# STM8S207R8T6_Header_Board.net
KiCad netlist of a schematic drawn in Altium Designer
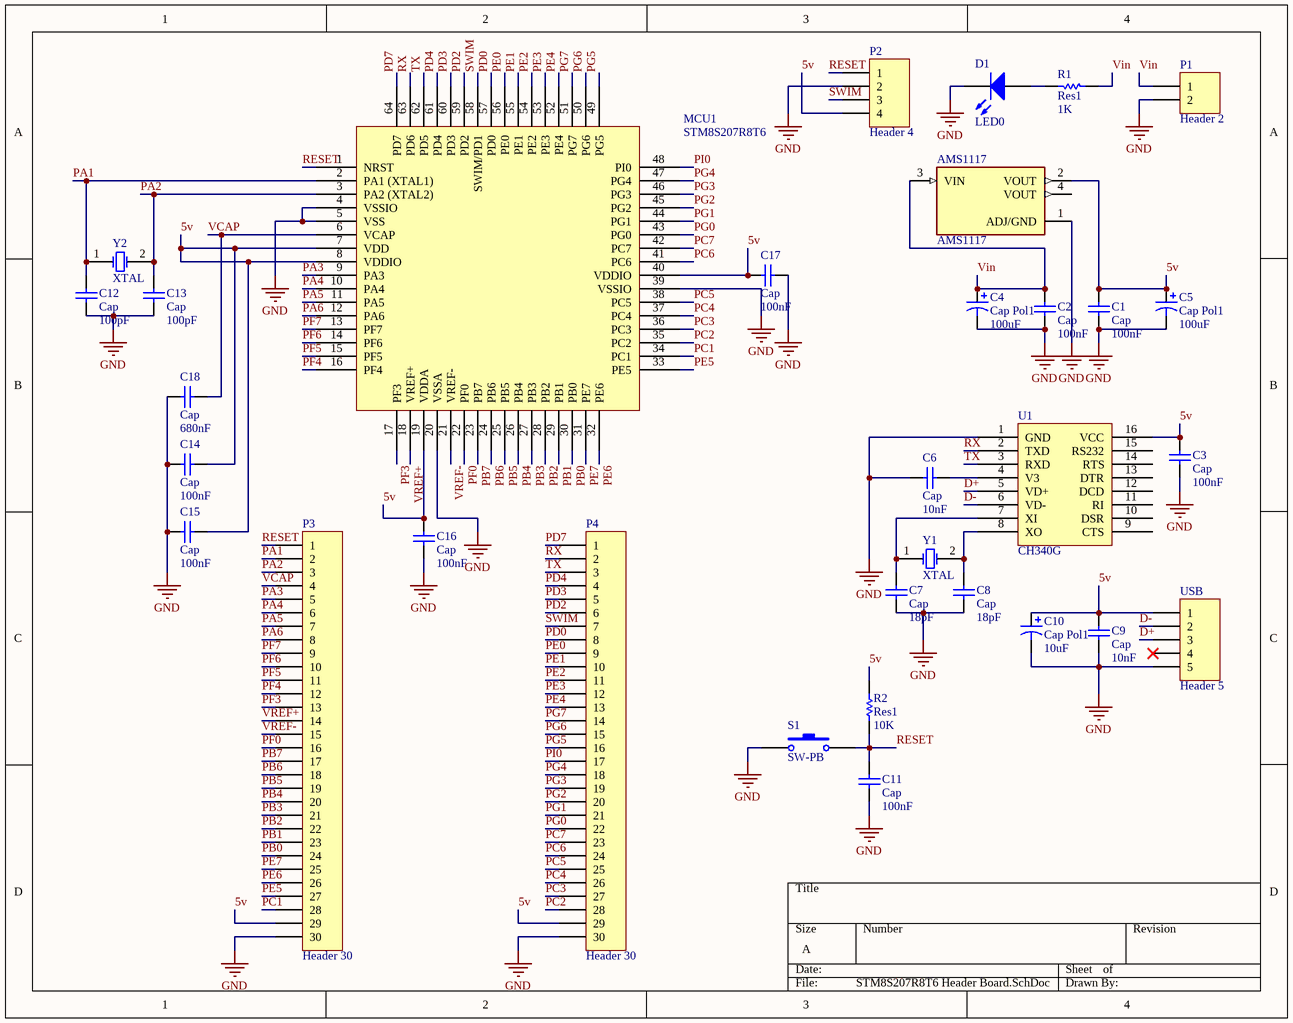
[diagram p0: STM8S207R8T6 Header Board.SchDoc]

(export (version "E")
  (design (tool "Eeschema 10.0.6"))
  (components
    (comp (ref "AMS1117")
      (value "AMS1117")
      (footprint "SOT229P700X180-4N")
      (description "UNO PLUS Arduino R3 Shield, Xbee Arduino IDE Wheeled Robotics Kit")
      (fields (field (name "MF") "Seeed Technology"))
      (libsource (lib "AMS1117") (part "AMS1117"))
    )
    (comp (ref "C1")
      (value "Cap")
      (footprint "6-0805_N")
      (description "Capacitor")
      (fields (field (name "ALTIUM_VALUE") "100nF") (field (name "PUBLISHER") "Altium Limited"))
      (libsource (lib "Miscellaneous Devices") (part "Cap"))
    )
    (comp (ref "C2")
      (value "Cap")
      (footprint "6-0805_N")
      (description "Capacitor")
      (fields (field (name "ALTIUM_VALUE") "100nF") (field (name "PUBLISHER") "Altium Limited"))
      (libsource (lib "Miscellaneous Devices") (part "Cap"))
    )
    (comp (ref "C3")
      (value "Cap")
      (footprint "6-0805_N")
      (description "Capacitor")
      (fields (field (name "ALTIUM_VALUE") "100nF") (field (name "PUBLISHER") "Altium Limited"))
      (libsource (lib "Miscellaneous Devices") (part "Cap"))
    )
    (comp (ref "C4")
      (value "Cap Pol1")
      (footprint "C1210_N")
      (description "Polarized Capacitor (Radial)")
      (fields (field (name "ALTIUM_VALUE") "100uF") (field (name "PUBLISHER") "Altium Limited"))
      (libsource (lib "Miscellaneous Devices") (part "Cap Pol1"))
    )
    (comp (ref "C5")
      (value "Cap Pol1")
      (footprint "C1210_N")
      (description "Polarized Capacitor (Radial)")
      (fields (field (name "ALTIUM_VALUE") "100uF") (field (name "PUBLISHER") "Altium Limited"))
      (libsource (lib "Miscellaneous Devices") (part "Cap Pol1"))
    )
    (comp (ref "C6")
      (value "Cap")
      (footprint "6-0805_N")
      (description "Capacitor")
      (fields (field (name "ALTIUM_VALUE") "10nF") (field (name "PUBLISHER") "Altium Limited"))
      (libsource (lib "Miscellaneous Devices") (part "Cap"))
    )
    (comp (ref "C7")
      (value "Cap")
      (footprint "6-0805_N")
      (description "Capacitor")
      (fields (field (name "ALTIUM_VALUE") "18pF") (field (name "PUBLISHER") "Altium Limited"))
      (libsource (lib "Miscellaneous Devices") (part "Cap"))
    )
    (comp (ref "C8")
      (value "Cap")
      (footprint "6-0805_N")
      (description "Capacitor")
      (fields (field (name "ALTIUM_VALUE") "18pF") (field (name "PUBLISHER") "Altium Limited"))
      (libsource (lib "Miscellaneous Devices") (part "Cap"))
    )
    (comp (ref "C9")
      (value "Cap")
      (footprint "6-0805_N")
      (description "Capacitor")
      (fields (field (name "ALTIUM_VALUE") "10nF") (field (name "PUBLISHER") "Altium Limited"))
      (libsource (lib "Miscellaneous Devices") (part "Cap"))
    )
    (comp (ref "C10")
      (value "Cap Pol1")
      (footprint "C1210_N")
      (description "Polarized Capacitor (Radial)")
      (fields (field (name "ALTIUM_VALUE") "10uF") (field (name "PUBLISHER") "Altium Limited"))
      (libsource (lib "Miscellaneous Devices") (part "Cap Pol1"))
    )
    (comp (ref "C11")
      (value "Cap")
      (footprint "6-0805_N")
      (description "Capacitor")
      (fields (field (name "ALTIUM_VALUE") "100nF") (field (name "PUBLISHER") "Altium Limited"))
      (libsource (lib "Miscellaneous Devices") (part "Cap"))
    )
    (comp (ref "C12")
      (value "Cap")
      (footprint "6-0805_N")
      (description "Capacitor")
      (fields (field (name "ALTIUM_VALUE") "100pF") (field (name "PUBLISHER") "Altium Limited"))
      (libsource (lib "Miscellaneous Devices") (part "Cap"))
    )
    (comp (ref "C13")
      (value "Cap")
      (footprint "6-0805_N")
      (description "Capacitor")
      (fields (field (name "ALTIUM_VALUE") "100pF") (field (name "PUBLISHER") "Altium Limited"))
      (libsource (lib "Miscellaneous Devices") (part "Cap"))
    )
    (comp (ref "C14")
      (value "Cap")
      (footprint "6-0805_N")
      (description "Capacitor")
      (fields (field (name "ALTIUM_VALUE") "100nF") (field (name "PUBLISHER") "Altium Limited"))
      (libsource (lib "Miscellaneous Devices") (part "Cap"))
    )
    (comp (ref "C15")
      (value "Cap")
      (footprint "6-0805_N")
      (description "Capacitor")
      (fields (field (name "ALTIUM_VALUE") "100nF") (field (name "PUBLISHER") "Altium Limited"))
      (libsource (lib "Miscellaneous Devices") (part "Cap"))
    )
    (comp (ref "C16")
      (value "Cap")
      (footprint "6-0805_N")
      (description "Capacitor")
      (fields (field (name "ALTIUM_VALUE") "100nF") (field (name "PUBLISHER") "Altium Limited"))
      (libsource (lib "Miscellaneous Devices") (part "Cap"))
    )
    (comp (ref "C17")
      (value "Cap")
      (footprint "6-0805_N")
      (description "Capacitor")
      (fields (field (name "ALTIUM_VALUE") "100nF") (field (name "PUBLISHER") "Altium Limited"))
      (libsource (lib "Miscellaneous Devices") (part "Cap"))
    )
    (comp (ref "C18")
      (value "Cap")
      (footprint "6-0805_N")
      (description "Capacitor")
      (fields (field (name "ALTIUM_VALUE") "680nF") (field (name "PUBLISHER") "Altium Limited"))
      (libsource (lib "Miscellaneous Devices") (part "Cap"))
    )
    (comp (ref "D1")
      (value "LED0")
      (footprint "6-0805_N")
      (description "Typical INFRARED GaAs LED")
      (fields (field (name "PUBLISHER") "Altium Limited"))
      (libsource (lib "Miscellaneous Devices") (part "LED0"))
    )
    (comp (ref "MCU1")
      (value "STM8S207R8T6")
      (footprint "QFP50P1200X1200X160-64N")
      (libsource (lib "STM8S207R8T6") (part "STM8S207R8T6"))
    )
    (comp (ref "P1")
      (value "Header 2")
      (footprint "Terminal2")
      (description "Header, 2-Pin")
      (fields (field (name "PUBLISHER") "Altium Limited"))
      (libsource (lib "Miscellaneous Connectors") (part "Header 2"))
    )
    (comp (ref "P2")
      (value "Header 4")
      (footprint "HDR1X4")
      (description "Header, 4-Pin")
      (fields (field (name "PUBLISHER") "Altium Limited"))
      (libsource (lib "Miscellaneous Connectors") (part "Header 4"))
    )
    (comp (ref "P3")
      (value "Header 30")
      (footprint "Header 30")
      (description "Header, 30-Pin")
      (fields (field (name "PUBLISHER") "Altium Limited"))
      (libsource (lib "Miscellaneous Connectors") (part "Header 30"))
    )
    (comp (ref "P4")
      (value "Header 30")
      (footprint "Header 30")
      (description "Header, 30-Pin")
      (fields (field (name "PUBLISHER") "Altium Limited"))
      (libsource (lib "Miscellaneous Connectors") (part "Header 30"))
    )
    (comp (ref "R1")
      (value "Res1")
      (footprint "6-0805_N")
      (description "Resistor")
      (fields (field (name "ALTIUM_VALUE") "1K") (field (name "PUBLISHER") "Altium Limited"))
      (libsource (lib "Miscellaneous Devices") (part "Res1"))
    )
    (comp (ref "R2")
      (value "Res1")
      (footprint "6-0805_N")
      (description "Resistor")
      (fields (field (name "ALTIUM_VALUE") "10K") (field (name "PUBLISHER") "Altium Limited"))
      (libsource (lib "Miscellaneous Devices") (part "Res1"))
    )
    (comp (ref "S1")
      (value "SW-PB")
      (footprint "RES_B")
      (description "Switch")
      (fields (field (name "PUBLISHER") "Altium Limited"))
      (libsource (lib "Miscellaneous Devices") (part "SW-PB"))
    )
    (comp (ref "U1")
      (value "CH340G")
      (footprint "SOIC127P600X175-16N")
      (libsource (lib "CH340") (part "CH340G"))
    )
    (comp (ref "USB")
      (value "Header 5")
      (footprint "TE_3-1734035-2")
      (description "Header, 5-Pin")
      (fields (field (name "PUBLISHER") "Altium Limited"))
      (libsource (lib "Miscellaneous Connectors") (part "Header 5"))
    )
    (comp (ref "Y1")
      (value "XTAL")
      (footprint "Xtal")
      (description "Crystal Oscillator")
      (fields (field (name "PUBLISHER") "Altium Limited"))
      (libsource (lib "Miscellaneous Devices") (part "XTAL"))
    )
    (comp (ref "Y2")
      (value "XTAL")
      (footprint "Xtal")
      (description "Crystal Oscillator")
      (fields (field (name "PUBLISHER") "Altium Limited"))
      (libsource (lib "Miscellaneous Devices") (part "XTAL"))
    )
  )
  (nets
    (net (code "1") (name "/5v") (class "Default")
      (node (ref "AMS1117") (pin "2") (pinfunction "VOUT_2") (pintype "output"))
      (node (ref "C1") (pin "2") (pinfunction "2_2") (pintype "passive"))
      (node (ref "C10") (pin "1") (pinfunction "1_1") (pintype "passive"))
      (node (ref "C14") (pin "1") (pinfunction "1_1") (pintype "passive"))
      (node (ref "C15") (pin "1") (pinfunction "1_1") (pintype "passive"))
      (node (ref "C16") (pin "2") (pinfunction "2_2") (pintype "passive"))
      (node (ref "C17") (pin "1") (pinfunction "1_1") (pintype "passive"))
      (node (ref "C3") (pin "1") (pinfunction "1_1") (pintype "passive"))
      (node (ref "C5") (pin "1") (pinfunction "1_1") (pintype "passive"))
      (node (ref "C9") (pin "2") (pinfunction "2_2") (pintype "passive"))
      (node (ref "MCU1") (pin "19") (pinfunction "VDDA_19") (pintype "passive"))
      (node (ref "MCU1") (pin "40") (pinfunction "VDDIO_40") (pintype "passive"))
      (node (ref "MCU1") (pin "7") (pinfunction "VDD_7") (pintype "passive"))
      (node (ref "MCU1") (pin "8") (pinfunction "VDDIO_8") (pintype "passive"))
      (node (ref "P2") (pin "4") (pinfunction "4_4") (pintype "passive"))
      (node (ref "P3") (pin "29") (pinfunction "29_29") (pintype "passive"))
      (node (ref "P4") (pin "29") (pinfunction "29_29") (pintype "passive"))
      (node (ref "R2") (pin "2") (pinfunction "2_2") (pintype "passive"))
      (node (ref "U1") (pin "16") (pinfunction "VCC_16") (pintype "passive"))
      (node (ref "USB") (pin "1") (pinfunction "1_1") (pintype "passive"))
    )
    (net (code "2") (name "/D+") (class "Default")
      (node (ref "U1") (pin "5") (pinfunction "VD+_5") (pintype "passive"))
      (node (ref "USB") (pin "3") (pinfunction "3_3") (pintype "passive"))
    )
    (net (code "3") (name "/D-") (class "Default")
      (node (ref "U1") (pin "6") (pinfunction "VD-_6") (pintype "passive"))
      (node (ref "USB") (pin "2") (pinfunction "2_2") (pintype "passive"))
    )
    (net (code "4") (name "/PA1") (class "Default")
      (node (ref "C12") (pin "2") (pinfunction "2_2") (pintype "passive"))
      (node (ref "MCU1") (pin "2") (pinfunction "PA1_(XTAL1)_2") (pintype "passive"))
      (node (ref "P3") (pin "2") (pinfunction "2_2") (pintype "passive"))
      (node (ref "Y2") (pin "1") (pinfunction "OSC1_1") (pintype "passive"))
    )
    (net (code "5") (name "/PA2") (class "Default")
      (node (ref "C13") (pin "2") (pinfunction "2_2") (pintype "passive"))
      (node (ref "MCU1") (pin "3") (pinfunction "PA2_(XTAL2)_3") (pintype "passive"))
      (node (ref "P3") (pin "3") (pinfunction "3_3") (pintype "passive"))
      (node (ref "Y2") (pin "2") (pinfunction "OSC2_2") (pintype "passive"))
    )
    (net (code "6") (name "/PA3") (class "Default")
      (node (ref "MCU1") (pin "9") (pinfunction "PA3_9") (pintype "passive"))
      (node (ref "P3") (pin "5") (pinfunction "5_5") (pintype "passive"))
    )
    (net (code "7") (name "/PA4") (class "Default")
      (node (ref "MCU1") (pin "10") (pinfunction "PA4_10") (pintype "passive"))
      (node (ref "P3") (pin "6") (pinfunction "6_6") (pintype "passive"))
    )
    (net (code "8") (name "/PA5") (class "Default")
      (node (ref "MCU1") (pin "11") (pinfunction "PA5_11") (pintype "passive"))
      (node (ref "P3") (pin "7") (pinfunction "7_7") (pintype "passive"))
    )
    (net (code "9") (name "/PA6") (class "Default")
      (node (ref "MCU1") (pin "12") (pinfunction "PA6_12") (pintype "passive"))
      (node (ref "P3") (pin "8") (pinfunction "8_8") (pintype "passive"))
    )
    (net (code "10") (name "/PB0") (class "Default")
      (node (ref "MCU1") (pin "30") (pinfunction "PB0_30") (pintype "passive"))
      (node (ref "P3") (pin "24") (pinfunction "24_24") (pintype "passive"))
    )
    (net (code "11") (name "/PB1") (class "Default")
      (node (ref "MCU1") (pin "29") (pinfunction "PB1_29") (pintype "passive"))
      (node (ref "P3") (pin "23") (pinfunction "23_23") (pintype "passive"))
    )
    (net (code "12") (name "/PB2") (class "Default")
      (node (ref "MCU1") (pin "28") (pinfunction "PB2_28") (pintype "passive"))
      (node (ref "P3") (pin "22") (pinfunction "22_22") (pintype "passive"))
    )
    (net (code "13") (name "/PB3") (class "Default")
      (node (ref "MCU1") (pin "27") (pinfunction "PB3_27") (pintype "passive"))
      (node (ref "P3") (pin "21") (pinfunction "21_21") (pintype "passive"))
    )
    (net (code "14") (name "/PB4") (class "Default")
      (node (ref "MCU1") (pin "26") (pinfunction "PB4_26") (pintype "passive"))
      (node (ref "P3") (pin "20") (pinfunction "20_20") (pintype "passive"))
    )
    (net (code "15") (name "/PB5") (class "Default")
      (node (ref "MCU1") (pin "25") (pinfunction "PB5_25") (pintype "passive"))
      (node (ref "P3") (pin "19") (pinfunction "19_19") (pintype "passive"))
    )
    (net (code "16") (name "/PB6") (class "Default")
      (node (ref "MCU1") (pin "24") (pinfunction "PB6_24") (pintype "passive"))
      (node (ref "P3") (pin "18") (pinfunction "18_18") (pintype "passive"))
    )
    (net (code "17") (name "/PB7") (class "Default")
      (node (ref "MCU1") (pin "23") (pinfunction "PB7_23") (pintype "passive"))
      (node (ref "P3") (pin "17") (pinfunction "17_17") (pintype "passive"))
    )
    (net (code "18") (name "/PC1") (class "Default")
      (node (ref "MCU1") (pin "34") (pinfunction "PC1_34") (pintype "passive"))
      (node (ref "P3") (pin "28") (pinfunction "28_28") (pintype "passive"))
    )
    (net (code "19") (name "/PC2") (class "Default")
      (node (ref "MCU1") (pin "35") (pinfunction "PC2_35") (pintype "passive"))
      (node (ref "P4") (pin "28") (pinfunction "28_28") (pintype "passive"))
    )
    (net (code "20") (name "/PC3") (class "Default")
      (node (ref "MCU1") (pin "36") (pinfunction "PC3_36") (pintype "passive"))
      (node (ref "P4") (pin "27") (pinfunction "27_27") (pintype "passive"))
    )
    (net (code "21") (name "/PC4") (class "Default")
      (node (ref "MCU1") (pin "37") (pinfunction "PC4_37") (pintype "passive"))
      (node (ref "P4") (pin "26") (pinfunction "26_26") (pintype "passive"))
    )
    (net (code "22") (name "/PC5") (class "Default")
      (node (ref "MCU1") (pin "38") (pinfunction "PC5_38") (pintype "passive"))
      (node (ref "P4") (pin "25") (pinfunction "25_25") (pintype "passive"))
    )
    (net (code "23") (name "/PC6") (class "Default")
      (node (ref "MCU1") (pin "41") (pinfunction "PC6_41") (pintype "passive"))
      (node (ref "P4") (pin "24") (pinfunction "24_24") (pintype "passive"))
    )
    (net (code "24") (name "/PC7") (class "Default")
      (node (ref "MCU1") (pin "42") (pinfunction "PC7_42") (pintype "passive"))
      (node (ref "P4") (pin "23") (pinfunction "23_23") (pintype "passive"))
    )
    (net (code "25") (name "/PD0") (class "Default")
      (node (ref "MCU1") (pin "57") (pinfunction "PD0_57") (pintype "passive"))
      (node (ref "P4") (pin "8") (pinfunction "8_8") (pintype "passive"))
    )
    (net (code "26") (name "/PD2") (class "Default")
      (node (ref "MCU1") (pin "59") (pinfunction "PD2_59") (pintype "passive"))
      (node (ref "P4") (pin "6") (pinfunction "6_6") (pintype "passive"))
    )
    (net (code "27") (name "/PD3") (class "Default")
      (node (ref "MCU1") (pin "60") (pinfunction "PD3_60") (pintype "passive"))
      (node (ref "P4") (pin "5") (pinfunction "5_5") (pintype "passive"))
    )
    (net (code "28") (name "/PD4") (class "Default")
      (node (ref "MCU1") (pin "61") (pinfunction "PD4_61") (pintype "passive"))
      (node (ref "P4") (pin "4") (pinfunction "4_4") (pintype "passive"))
    )
    (net (code "29") (name "/PD7") (class "Default")
      (node (ref "MCU1") (pin "64") (pinfunction "PD7_64") (pintype "passive"))
      (node (ref "P4") (pin "1") (pinfunction "1_1") (pintype "passive"))
    )
    (net (code "30") (name "/PE0") (class "Default")
      (node (ref "MCU1") (pin "56") (pinfunction "PE0_56") (pintype "passive"))
      (node (ref "P4") (pin "9") (pinfunction "9_9") (pintype "passive"))
    )
    (net (code "31") (name "/PE1") (class "Default")
      (node (ref "MCU1") (pin "55") (pinfunction "PE1_55") (pintype "passive"))
      (node (ref "P4") (pin "10") (pinfunction "10_10") (pintype "passive"))
    )
    (net (code "32") (name "/PE2") (class "Default")
      (node (ref "MCU1") (pin "54") (pinfunction "PE2_54") (pintype "passive"))
      (node (ref "P4") (pin "11") (pinfunction "11_11") (pintype "passive"))
    )
    (net (code "33") (name "/PE3") (class "Default")
      (node (ref "MCU1") (pin "53") (pinfunction "PE3_53") (pintype "passive"))
      (node (ref "P4") (pin "12") (pinfunction "12_12") (pintype "passive"))
    )
    (net (code "34") (name "/PE4") (class "Default")
      (node (ref "MCU1") (pin "52") (pinfunction "PE4_52") (pintype "passive"))
      (node (ref "P4") (pin "13") (pinfunction "13_13") (pintype "passive"))
    )
    (net (code "35") (name "/PE5") (class "Default")
      (node (ref "MCU1") (pin "33") (pinfunction "PE5_33") (pintype "passive"))
      (node (ref "P3") (pin "27") (pinfunction "27_27") (pintype "passive"))
    )
    (net (code "36") (name "/PE6") (class "Default")
      (node (ref "MCU1") (pin "32") (pinfunction "PE6_32") (pintype "passive"))
      (node (ref "P3") (pin "26") (pinfunction "26_26") (pintype "passive"))
    )
    (net (code "37") (name "/PE7") (class "Default")
      (node (ref "MCU1") (pin "31") (pinfunction "PE7_31") (pintype "passive"))
      (node (ref "P3") (pin "25") (pinfunction "25_25") (pintype "passive"))
    )
    (net (code "38") (name "/PF0") (class "Default")
      (node (ref "MCU1") (pin "22") (pinfunction "PF0_22") (pintype "passive"))
      (node (ref "P3") (pin "16") (pinfunction "16_16") (pintype "passive"))
    )
    (net (code "39") (name "/PF3") (class "Default")
      (node (ref "MCU1") (pin "17") (pinfunction "PF3_17") (pintype "passive"))
      (node (ref "P3") (pin "13") (pinfunction "13_13") (pintype "passive"))
    )
    (net (code "40") (name "/PF4") (class "Default")
      (node (ref "MCU1") (pin "16") (pinfunction "PF4_16") (pintype "passive"))
      (node (ref "P3") (pin "12") (pinfunction "12_12") (pintype "passive"))
    )
    (net (code "41") (name "/PF5") (class "Default")
      (node (ref "MCU1") (pin "15") (pinfunction "PF5_15") (pintype "passive"))
      (node (ref "P3") (pin "11") (pinfunction "11_11") (pintype "passive"))
    )
    (net (code "42") (name "/PF6") (class "Default")
      (node (ref "MCU1") (pin "14") (pinfunction "PF6_14") (pintype "passive"))
      (node (ref "P3") (pin "10") (pinfunction "10_10") (pintype "passive"))
    )
    (net (code "43") (name "/PF7") (class "Default")
      (node (ref "MCU1") (pin "13") (pinfunction "PF7_13") (pintype "passive"))
      (node (ref "P3") (pin "9") (pinfunction "9_9") (pintype "passive"))
    )
    (net (code "44") (name "/PG0") (class "Default")
      (node (ref "MCU1") (pin "43") (pinfunction "PG0_43") (pintype "passive"))
      (node (ref "P4") (pin "22") (pinfunction "22_22") (pintype "passive"))
    )
    (net (code "45") (name "/PG1") (class "Default")
      (node (ref "MCU1") (pin "44") (pinfunction "PG1_44") (pintype "passive"))
      (node (ref "P4") (pin "21") (pinfunction "21_21") (pintype "passive"))
    )
    (net (code "46") (name "/PG2") (class "Default")
      (node (ref "MCU1") (pin "45") (pinfunction "PG2_45") (pintype "passive"))
      (node (ref "P4") (pin "20") (pinfunction "20_20") (pintype "passive"))
    )
    (net (code "47") (name "/PG3") (class "Default")
      (node (ref "MCU1") (pin "46") (pinfunction "PG3_46") (pintype "passive"))
      (node (ref "P4") (pin "19") (pinfunction "19_19") (pintype "passive"))
    )
    (net (code "48") (name "/PG4") (class "Default")
      (node (ref "MCU1") (pin "47") (pinfunction "PG4_47") (pintype "passive"))
      (node (ref "P4") (pin "18") (pinfunction "18_18") (pintype "passive"))
    )
    (net (code "49") (name "/PG5") (class "Default")
      (node (ref "MCU1") (pin "49") (pinfunction "PG5_49") (pintype "passive"))
      (node (ref "P4") (pin "16") (pinfunction "16_16") (pintype "passive"))
    )
    (net (code "50") (name "/PG6") (class "Default")
      (node (ref "MCU1") (pin "50") (pinfunction "PG6_50") (pintype "passive"))
      (node (ref "P4") (pin "15") (pinfunction "15_15") (pintype "passive"))
    )
    (net (code "51") (name "/PG7") (class "Default")
      (node (ref "MCU1") (pin "51") (pinfunction "PG7_51") (pintype "passive"))
      (node (ref "P4") (pin "14") (pinfunction "14_14") (pintype "passive"))
    )
    (net (code "52") (name "/PI0") (class "Default")
      (node (ref "MCU1") (pin "48") (pinfunction "PI0_48") (pintype "passive"))
      (node (ref "P4") (pin "17") (pinfunction "17_17") (pintype "passive"))
    )
    (net (code "53") (name "/RESET") (class "Default")
      (node (ref "C11") (pin "2") (pinfunction "2_2") (pintype "passive"))
      (node (ref "MCU1") (pin "1") (pinfunction "NRST_1") (pintype "passive"))
      (node (ref "P2") (pin "1") (pinfunction "1_1") (pintype "passive"))
      (node (ref "P3") (pin "1") (pinfunction "1_1") (pintype "passive"))
      (node (ref "R2") (pin "1") (pinfunction "1_1") (pintype "passive"))
      (node (ref "S1") (pin "2") (pinfunction "2_2") (pintype "passive"))
    )
    (net (code "54") (name "/RX") (class "Default")
      (node (ref "MCU1") (pin "63") (pinfunction "PD6_63") (pintype "passive"))
      (node (ref "P4") (pin "2") (pinfunction "2_2") (pintype "passive"))
      (node (ref "U1") (pin "2") (pinfunction "TXD_2") (pintype "passive"))
    )
    (net (code "55") (name "/SWIM") (class "Default")
      (node (ref "MCU1") (pin "58") (pinfunction "SWIM/PD1_58") (pintype "passive"))
      (node (ref "P2") (pin "3") (pinfunction "3_3") (pintype "passive"))
      (node (ref "P4") (pin "7") (pinfunction "7_7") (pintype "passive"))
    )
    (net (code "56") (name "/TX") (class "Default")
      (node (ref "MCU1") (pin "62") (pinfunction "PD5_62") (pintype "passive"))
      (node (ref "P4") (pin "3") (pinfunction "3_3") (pintype "passive"))
      (node (ref "U1") (pin "3") (pinfunction "RXD_3") (pintype "passive"))
    )
    (net (code "57") (name "/VCAP") (class "Default")
      (node (ref "C18") (pin "1") (pinfunction "1_1") (pintype "passive"))
      (node (ref "MCU1") (pin "6") (pinfunction "VCAP_6") (pintype "passive"))
      (node (ref "P3") (pin "4") (pinfunction "4_4") (pintype "passive"))
    )
    (net (code "58") (name "/VREF+") (class "Default")
      (node (ref "MCU1") (pin "18") (pinfunction "VREF+_18") (pintype "passive"))
      (node (ref "P3") (pin "14") (pinfunction "14_14") (pintype "passive"))
    )
    (net (code "59") (name "/VREF-") (class "Default")
      (node (ref "MCU1") (pin "21") (pinfunction "VREF-_21") (pintype "passive"))
      (node (ref "P3") (pin "15") (pinfunction "15_15") (pintype "passive"))
    )
    (net (code "60") (name "/Vin") (class "Default")
      (node (ref "AMS1117") (pin "3") (pinfunction "VIN_3") (pintype "input"))
      (node (ref "C2") (pin "2") (pinfunction "2_2") (pintype "passive"))
      (node (ref "C4") (pin "1") (pinfunction "1_1") (pintype "passive"))
      (node (ref "P1") (pin "1") (pinfunction "1_1") (pintype "passive"))
      (node (ref "R1") (pin "1") (pinfunction "1_1") (pintype "passive"))
    )
    (net (code "61") (name "GND") (class "Default")
      (node (ref "AMS1117") (pin "1") (pinfunction "ADJ/GND_1") (pintype "power_in"))
      (node (ref "C1") (pin "1") (pinfunction "1_1") (pintype "passive"))
      (node (ref "C10") (pin "2") (pinfunction "2_2") (pintype "passive"))
      (node (ref "C11") (pin "1") (pinfunction "1_1") (pintype "passive"))
      (node (ref "C12") (pin "1") (pinfunction "1_1") (pintype "passive"))
      (node (ref "C13") (pin "1") (pinfunction "1_1") (pintype "passive"))
      (node (ref "C14") (pin "2") (pinfunction "2_2") (pintype "passive"))
      (node (ref "C15") (pin "2") (pinfunction "2_2") (pintype "passive"))
      (node (ref "C16") (pin "1") (pinfunction "1_1") (pintype "passive"))
      (node (ref "C17") (pin "2") (pinfunction "2_2") (pintype "passive"))
      (node (ref "C18") (pin "2") (pinfunction "2_2") (pintype "passive"))
      (node (ref "C2") (pin "1") (pinfunction "1_1") (pintype "passive"))
      (node (ref "C3") (pin "2") (pinfunction "2_2") (pintype "passive"))
      (node (ref "C4") (pin "2") (pinfunction "2_2") (pintype "passive"))
      (node (ref "C5") (pin "2") (pinfunction "2_2") (pintype "passive"))
      (node (ref "C6") (pin "1") (pinfunction "1_1") (pintype "passive"))
      (node (ref "C7") (pin "1") (pinfunction "1_1") (pintype "passive"))
      (node (ref "C8") (pin "1") (pinfunction "1_1") (pintype "passive"))
      (node (ref "C9") (pin "1") (pinfunction "1_1") (pintype "passive"))
      (node (ref "D1") (pin "2") (pinfunction "K_2") (pintype "passive"))
      (node (ref "MCU1") (pin "20") (pinfunction "VSSA_20") (pintype "passive"))
      (node (ref "MCU1") (pin "39") (pinfunction "VSSIO_39") (pintype "passive"))
      (node (ref "MCU1") (pin "4") (pinfunction "VSSIO_4") (pintype "passive"))
      (node (ref "MCU1") (pin "5") (pinfunction "VSS_5") (pintype "passive"))
      (node (ref "P1") (pin "2") (pinfunction "2_2") (pintype "passive"))
      (node (ref "P2") (pin "2") (pinfunction "2_2") (pintype "passive"))
      (node (ref "P3") (pin "30") (pinfunction "30_30") (pintype "passive"))
      (node (ref "P4") (pin "30") (pinfunction "30_30") (pintype "passive"))
      (node (ref "S1") (pin "1") (pinfunction "1_1") (pintype "passive"))
      (node (ref "U1") (pin "1") (pinfunction "GND_1") (pintype "passive"))
      (node (ref "USB") (pin "5") (pinfunction "5_5") (pintype "passive"))
    )
    (net (code "62") (name "Net-(D1-A)") (class "Default")
      (node (ref "D1") (pin "1") (pinfunction "A_1") (pintype "passive"))
      (node (ref "R1") (pin "2") (pinfunction "2_2") (pintype "passive"))
    )
    (net (code "63") (name "Net-(U1-V3)") (class "Default")
      (node (ref "C6") (pin "2") (pinfunction "2_2") (pintype "passive"))
      (node (ref "U1") (pin "4") (pinfunction "V3_4") (pintype "passive"))
    )
    (net (code "64") (name "Net-(U1-XI)") (class "Default")
      (node (ref "C7") (pin "2") (pinfunction "2_2") (pintype "passive"))
      (node (ref "U1") (pin "7") (pinfunction "XI_7") (pintype "passive"))
      (node (ref "Y1") (pin "1") (pinfunction "OSC1_1") (pintype "passive"))
    )
    (net (code "65") (name "Net-(U1-XO)") (class "Default")
      (node (ref "C8") (pin "2") (pinfunction "2_2") (pintype "passive"))
      (node (ref "U1") (pin "8") (pinfunction "XO_8") (pintype "passive"))
      (node (ref "Y1") (pin "2") (pinfunction "OSC2_2") (pintype "passive"))
    )
    (net (code "66") (name "unconnected-(AMS1117-VOUT-Pad4)") (class "Default")
      (node (ref "AMS1117") (pin "4") (pinfunction "VOUT_4") (pintype "output"))
    )
    (net (code "67") (name "unconnected-(U1-CTS-Pad9)") (class "Default")
      (node (ref "U1") (pin "9") (pinfunction "CTS_9") (pintype "passive"))
    )
    (net (code "68") (name "unconnected-(U1-DCD-Pad12)") (class "Default")
      (node (ref "U1") (pin "12") (pinfunction "DCD_12") (pintype "passive"))
    )
    (net (code "69") (name "unconnected-(U1-DSR-Pad10)") (class "Default")
      (node (ref "U1") (pin "10") (pinfunction "DSR_10") (pintype "passive"))
    )
    (net (code "70") (name "unconnected-(U1-DTR-Pad13)") (class "Default")
      (node (ref "U1") (pin "13") (pinfunction "DTR_13") (pintype "passive"))
    )
    (net (code "71") (name "unconnected-(U1-RI-Pad11)") (class "Default")
      (node (ref "U1") (pin "11") (pinfunction "RI_11") (pintype "passive"))
    )
    (net (code "72") (name "unconnected-(U1-RS232-Pad15)") (class "Default")
      (node (ref "U1") (pin "15") (pinfunction "RS232_15") (pintype "passive"))
    )
    (net (code "73") (name "unconnected-(U1-RTS-Pad14)") (class "Default")
      (node (ref "U1") (pin "14") (pinfunction "RTS_14") (pintype "passive"))
    )
    (net (code "74") (name "unconnected-(USB-Pad4)") (class "Default")
      (node (ref "USB") (pin "4") (pinfunction "4_4") (pintype "passive+no_connect"))
    )
  )
)
